# 9button-9neopixel.net
KiCad netlist of a schematic drawn in Altium Designer
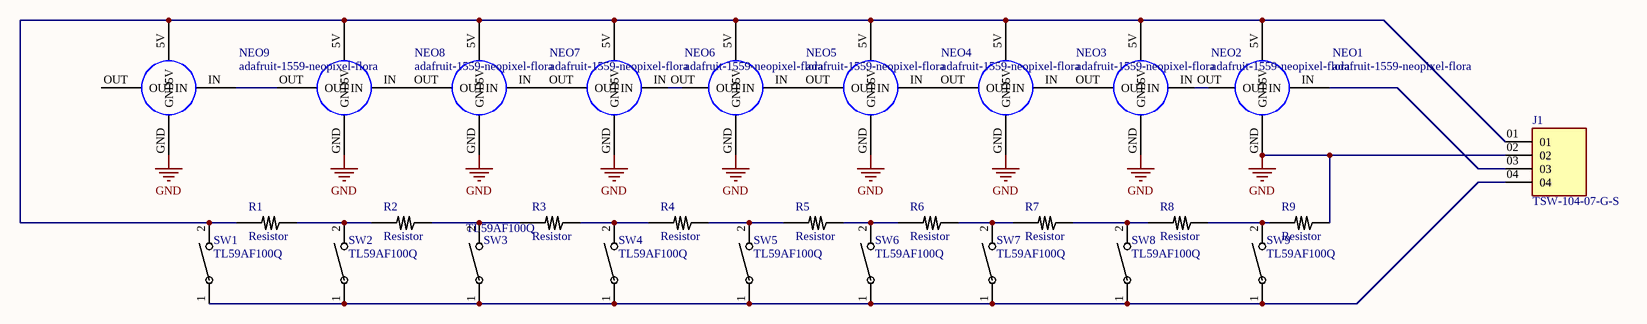
[diagram p0: 9button-9neopixel.SchDoc]

(export (version "E")
  (design (tool "Eeschema 10.0.6"))
  (components
    (comp (ref "J1")
      (value "TSW-104-07-G-S")
      (footprint "SAMTEC_TSW-104-07-G-S")
      (fields (field (name "MP") "altium_native_batch"))
      (libsource (lib "SchlibLafe") (part "TSW-104-07-G-S"))
    )
    (comp (ref "NEO1")
      (value "adafruit-1559-neopixel-flora")
      (footprint "adafruit-1559-neopixel-flora")
      (libsource (lib "SchlibLafe") (part "adafruit-1559-neopixel-flora"))
    )
    (comp (ref "NEO2")
      (value "adafruit-1559-neopixel-flora")
      (footprint "adafruit-1559-neopixel-flora")
      (libsource (lib "SchlibLafe") (part "adafruit-1559-neopixel-flora"))
    )
    (comp (ref "NEO3")
      (value "adafruit-1559-neopixel-flora")
      (footprint "adafruit-1559-neopixel-flora")
      (libsource (lib "SchlibLafe") (part "adafruit-1559-neopixel-flora"))
    )
    (comp (ref "NEO4")
      (value "adafruit-1559-neopixel-flora")
      (footprint "adafruit-1559-neopixel-flora")
      (libsource (lib "SchlibLafe") (part "adafruit-1559-neopixel-flora"))
    )
    (comp (ref "NEO5")
      (value "adafruit-1559-neopixel-flora")
      (footprint "adafruit-1559-neopixel-flora")
      (libsource (lib "SchlibLafe") (part "adafruit-1559-neopixel-flora"))
    )
    (comp (ref "NEO6")
      (value "adafruit-1559-neopixel-flora")
      (footprint "adafruit-1559-neopixel-flora")
      (libsource (lib "SchlibLafe") (part "adafruit-1559-neopixel-flora"))
    )
    (comp (ref "NEO7")
      (value "adafruit-1559-neopixel-flora")
      (footprint "adafruit-1559-neopixel-flora")
      (libsource (lib "SchlibLafe") (part "adafruit-1559-neopixel-flora"))
    )
    (comp (ref "NEO8")
      (value "adafruit-1559-neopixel-flora")
      (footprint "adafruit-1559-neopixel-flora")
      (libsource (lib "SchlibLafe") (part "adafruit-1559-neopixel-flora"))
    )
    (comp (ref "NEO9")
      (value "adafruit-1559-neopixel-flora")
      (footprint "adafruit-1559-neopixel-flora")
      (libsource (lib "SchlibLafe") (part "adafruit-1559-neopixel-flora"))
    )
    (comp (ref "R1")
      (value "Resistor")
      (footprint "thruhole resistor")
      (libsource (lib "SchlibLafe") (part "Resistor"))
    )
    (comp (ref "R2")
      (value "Resistor")
      (footprint "thruhole resistor")
      (libsource (lib "SchlibLafe") (part "Resistor"))
    )
    (comp (ref "R3")
      (value "Resistor")
      (footprint "thruhole resistor")
      (libsource (lib "SchlibLafe") (part "Resistor"))
    )
    (comp (ref "R4")
      (value "Resistor")
      (footprint "thruhole resistor")
      (libsource (lib "SchlibLafe") (part "Resistor"))
    )
    (comp (ref "R5")
      (value "Resistor")
      (footprint "thruhole resistor")
      (libsource (lib "SchlibLafe") (part "Resistor"))
    )
    (comp (ref "R6")
      (value "Resistor")
      (footprint "thruhole resistor")
      (libsource (lib "SchlibLafe") (part "Resistor"))
    )
    (comp (ref "R7")
      (value "Resistor")
      (footprint "thruhole resistor")
      (libsource (lib "SchlibLafe") (part "Resistor"))
    )
    (comp (ref "R8")
      (value "Resistor")
      (footprint "thruhole resistor")
      (libsource (lib "SchlibLafe") (part "Resistor"))
    )
    (comp (ref "R9")
      (value "Resistor")
      (footprint "thruhole resistor")
      (libsource (lib "SchlibLafe") (part "Resistor"))
    )
    (comp (ref "SW1")
      (value "TL59AF100Q")
      (footprint "SW_TL59AF100Q_EWI")
      (description "No Description Available")
      (fields (field (name "COPYRIGHT") "Copyright (C) 2024 Ultra Librarian. All rights reserved."))
      (libsource (lib "SchlibLafe") (part "TL59AF100Q"))
    )
    (comp (ref "SW2")
      (value "TL59AF100Q")
      (footprint "SW_TL59AF100Q_EWI")
      (description "No Description Available")
      (fields (field (name "COPYRIGHT") "Copyright (C) 2024 Ultra Librarian. All rights reserved."))
      (libsource (lib "SchlibLafe") (part "TL59AF100Q"))
    )
    (comp (ref "SW3")
      (value "TL59AF100Q")
      (footprint "SW_TL59AF100Q_EWI")
      (description "No Description Available")
      (fields (field (name "COPYRIGHT") "Copyright (C) 2024 Ultra Librarian. All rights reserved."))
      (libsource (lib "SchlibLafe") (part "TL59AF100Q"))
    )
    (comp (ref "SW4")
      (value "TL59AF100Q")
      (footprint "SW_TL59AF100Q_EWI")
      (description "No Description Available")
      (fields (field (name "COPYRIGHT") "Copyright (C) 2024 Ultra Librarian. All rights reserved."))
      (libsource (lib "SchlibLafe") (part "TL59AF100Q"))
    )
    (comp (ref "SW5")
      (value "TL59AF100Q")
      (footprint "SW_TL59AF100Q_EWI")
      (description "No Description Available")
      (fields (field (name "COPYRIGHT") "Copyright (C) 2024 Ultra Librarian. All rights reserved."))
      (libsource (lib "SchlibLafe") (part "TL59AF100Q"))
    )
    (comp (ref "SW6")
      (value "TL59AF100Q")
      (footprint "SW_TL59AF100Q_EWI")
      (description "No Description Available")
      (fields (field (name "COPYRIGHT") "Copyright (C) 2024 Ultra Librarian. All rights reserved."))
      (libsource (lib "SchlibLafe") (part "TL59AF100Q"))
    )
    (comp (ref "SW7")
      (value "TL59AF100Q")
      (footprint "SW_TL59AF100Q_EWI")
      (description "No Description Available")
      (fields (field (name "COPYRIGHT") "Copyright (C) 2024 Ultra Librarian. All rights reserved."))
      (libsource (lib "SchlibLafe") (part "TL59AF100Q"))
    )
    (comp (ref "SW8")
      (value "TL59AF100Q")
      (footprint "SW_TL59AF100Q_EWI")
      (description "No Description Available")
      (fields (field (name "COPYRIGHT") "Copyright (C) 2024 Ultra Librarian. All rights reserved."))
      (libsource (lib "SchlibLafe") (part "TL59AF100Q"))
    )
    (comp (ref "SW9")
      (value "TL59AF100Q")
      (footprint "SW_TL59AF100Q_EWI")
      (description "No Description Available")
      (fields (field (name "COPYRIGHT") "Copyright (C) 2024 Ultra Librarian. All rights reserved."))
      (libsource (lib "SchlibLafe") (part "TL59AF100Q"))
    )
  )
  (nets
    (net (code "1") (name "GND") (class "Default")
      (node (ref "J1") (pin "02") (pinfunction "02_02") (pintype "passive"))
      (node (ref "NEO1") (pin "GND") (pinfunction "GND_GND") (pintype "passive"))
      (node (ref "NEO2") (pin "GND") (pinfunction "GND_GND") (pintype "passive"))
      (node (ref "NEO3") (pin "GND") (pinfunction "GND_GND") (pintype "passive"))
      (node (ref "NEO4") (pin "GND") (pinfunction "GND_GND") (pintype "passive"))
      (node (ref "NEO5") (pin "GND") (pinfunction "GND_GND") (pintype "passive"))
      (node (ref "NEO6") (pin "GND") (pinfunction "GND_GND") (pintype "passive"))
      (node (ref "NEO7") (pin "GND") (pinfunction "GND_GND") (pintype "passive"))
      (node (ref "NEO8") (pin "GND") (pinfunction "GND_GND") (pintype "passive"))
      (node (ref "NEO9") (pin "GND") (pinfunction "GND_GND") (pintype "passive"))
      (node (ref "R9") (pin "1") (pinfunction "1_1") (pintype "passive"))
    )
    (net (code "2") (name "Net-(J1-Pad01)") (class "Default")
      (node (ref "J1") (pin "01") (pinfunction "01_01") (pintype "passive"))
      (node (ref "NEO1") (pin "5V") (pinfunction "5V_5V") (pintype "passive"))
      (node (ref "NEO2") (pin "5V") (pinfunction "5V_5V") (pintype "passive"))
      (node (ref "NEO3") (pin "5V") (pinfunction "5V_5V") (pintype "passive"))
      (node (ref "NEO4") (pin "5V") (pinfunction "5V_5V") (pintype "passive"))
      (node (ref "NEO5") (pin "5V") (pinfunction "5V_5V") (pintype "passive"))
      (node (ref "NEO6") (pin "5V") (pinfunction "5V_5V") (pintype "passive"))
      (node (ref "NEO7") (pin "5V") (pinfunction "5V_5V") (pintype "passive"))
      (node (ref "NEO8") (pin "5V") (pinfunction "5V_5V") (pintype "passive"))
      (node (ref "NEO9") (pin "5V") (pinfunction "5V_5V") (pintype "passive"))
      (node (ref "R1") (pin "2") (pinfunction "2_2") (pintype "passive"))
      (node (ref "SW1") (pin "2") (pinfunction "2_2") (pintype "passive"))
    )
    (net (code "3") (name "Net-(J1-Pad03)") (class "Default")
      (node (ref "J1") (pin "03") (pinfunction "03_03") (pintype "passive"))
      (node (ref "NEO1") (pin "IN") (pinfunction "IN_IN") (pintype "passive"))
    )
    (net (code "4") (name "Net-(J1-Pad04)") (class "Default")
      (node (ref "J1") (pin "04") (pinfunction "04_04") (pintype "passive"))
      (node (ref "SW1") (pin "1") (pinfunction "1_1") (pintype "passive"))
      (node (ref "SW2") (pin "1") (pinfunction "1_1") (pintype "passive"))
      (node (ref "SW3") (pin "1") (pinfunction "1_1") (pintype "passive"))
      (node (ref "SW4") (pin "1") (pinfunction "1_1") (pintype "passive"))
      (node (ref "SW5") (pin "1") (pinfunction "1_1") (pintype "passive"))
      (node (ref "SW6") (pin "1") (pinfunction "1_1") (pintype "passive"))
      (node (ref "SW7") (pin "1") (pinfunction "1_1") (pintype "passive"))
      (node (ref "SW8") (pin "1") (pinfunction "1_1") (pintype "passive"))
      (node (ref "SW9") (pin "1") (pinfunction "1_1") (pintype "passive"))
    )
    (net (code "5") (name "Net-(NEO1-PadOUT)") (class "Default")
      (node (ref "NEO1") (pin "OUT") (pinfunction "OUT_OUT") (pintype "passive"))
      (node (ref "NEO2") (pin "IN") (pinfunction "IN_IN") (pintype "passive"))
    )
    (net (code "6") (name "Net-(NEO2-PadOUT)") (class "Default")
      (node (ref "NEO2") (pin "OUT") (pinfunction "OUT_OUT") (pintype "passive"))
      (node (ref "NEO3") (pin "IN") (pinfunction "IN_IN") (pintype "passive"))
    )
    (net (code "7") (name "Net-(NEO3-PadOUT)") (class "Default")
      (node (ref "NEO3") (pin "OUT") (pinfunction "OUT_OUT") (pintype "passive"))
      (node (ref "NEO4") (pin "IN") (pinfunction "IN_IN") (pintype "passive"))
    )
    (net (code "8") (name "Net-(NEO4-PadOUT)") (class "Default")
      (node (ref "NEO4") (pin "OUT") (pinfunction "OUT_OUT") (pintype "passive"))
      (node (ref "NEO5") (pin "IN") (pinfunction "IN_IN") (pintype "passive"))
    )
    (net (code "9") (name "Net-(NEO5-PadOUT)") (class "Default")
      (node (ref "NEO5") (pin "OUT") (pinfunction "OUT_OUT") (pintype "passive"))
      (node (ref "NEO6") (pin "IN") (pinfunction "IN_IN") (pintype "passive"))
    )
    (net (code "10") (name "Net-(NEO6-PadOUT)") (class "Default")
      (node (ref "NEO6") (pin "OUT") (pinfunction "OUT_OUT") (pintype "passive"))
      (node (ref "NEO7") (pin "IN") (pinfunction "IN_IN") (pintype "passive"))
    )
    (net (code "11") (name "Net-(NEO7-PadOUT)") (class "Default")
      (node (ref "NEO7") (pin "OUT") (pinfunction "OUT_OUT") (pintype "passive"))
      (node (ref "NEO8") (pin "IN") (pinfunction "IN_IN") (pintype "passive"))
    )
    (net (code "12") (name "Net-(NEO8-PadOUT)") (class "Default")
      (node (ref "NEO8") (pin "OUT") (pinfunction "OUT_OUT") (pintype "passive"))
      (node (ref "NEO9") (pin "IN") (pinfunction "IN_IN") (pintype "passive"))
    )
    (net (code "13") (name "Net-(R1-Pad1)") (class "Default")
      (node (ref "R1") (pin "1") (pinfunction "1_1") (pintype "passive"))
      (node (ref "R2") (pin "2") (pinfunction "2_2") (pintype "passive"))
      (node (ref "SW2") (pin "2") (pinfunction "2_2") (pintype "passive"))
    )
    (net (code "14") (name "Net-(R2-Pad1)") (class "Default")
      (node (ref "R2") (pin "1") (pinfunction "1_1") (pintype "passive"))
      (node (ref "R3") (pin "2") (pinfunction "2_2") (pintype "passive"))
      (node (ref "SW3") (pin "2") (pinfunction "2_2") (pintype "passive"))
    )
    (net (code "15") (name "Net-(R3-Pad1)") (class "Default")
      (node (ref "R3") (pin "1") (pinfunction "1_1") (pintype "passive"))
      (node (ref "R4") (pin "2") (pinfunction "2_2") (pintype "passive"))
      (node (ref "SW4") (pin "2") (pinfunction "2_2") (pintype "passive"))
    )
    (net (code "16") (name "Net-(R4-Pad1)") (class "Default")
      (node (ref "R4") (pin "1") (pinfunction "1_1") (pintype "passive"))
      (node (ref "R5") (pin "2") (pinfunction "2_2") (pintype "passive"))
      (node (ref "SW5") (pin "2") (pinfunction "2_2") (pintype "passive"))
    )
    (net (code "17") (name "Net-(R5-Pad1)") (class "Default")
      (node (ref "R5") (pin "1") (pinfunction "1_1") (pintype "passive"))
      (node (ref "R6") (pin "2") (pinfunction "2_2") (pintype "passive"))
      (node (ref "SW6") (pin "2") (pinfunction "2_2") (pintype "passive"))
    )
    (net (code "18") (name "Net-(R6-Pad1)") (class "Default")
      (node (ref "R6") (pin "1") (pinfunction "1_1") (pintype "passive"))
      (node (ref "R7") (pin "2") (pinfunction "2_2") (pintype "passive"))
      (node (ref "SW7") (pin "2") (pinfunction "2_2") (pintype "passive"))
    )
    (net (code "19") (name "Net-(R7-Pad1)") (class "Default")
      (node (ref "R7") (pin "1") (pinfunction "1_1") (pintype "passive"))
      (node (ref "R8") (pin "2") (pinfunction "2_2") (pintype "passive"))
      (node (ref "SW8") (pin "2") (pinfunction "2_2") (pintype "passive"))
    )
    (net (code "20") (name "Net-(R8-Pad1)") (class "Default")
      (node (ref "R8") (pin "1") (pinfunction "1_1") (pintype "passive"))
      (node (ref "R9") (pin "2") (pinfunction "2_2") (pintype "passive"))
      (node (ref "SW9") (pin "2") (pinfunction "2_2") (pintype "passive"))
    )
    (net (code "21") (name "unconnected-(NEO9-PadOUT)") (class "Default")
      (node (ref "NEO9") (pin "OUT") (pinfunction "OUT_OUT") (pintype "passive"))
    )
  )
)
